# Bee_Hive_Scale_Board.net
KiCad netlist of a schematic drawn in Altium Designer
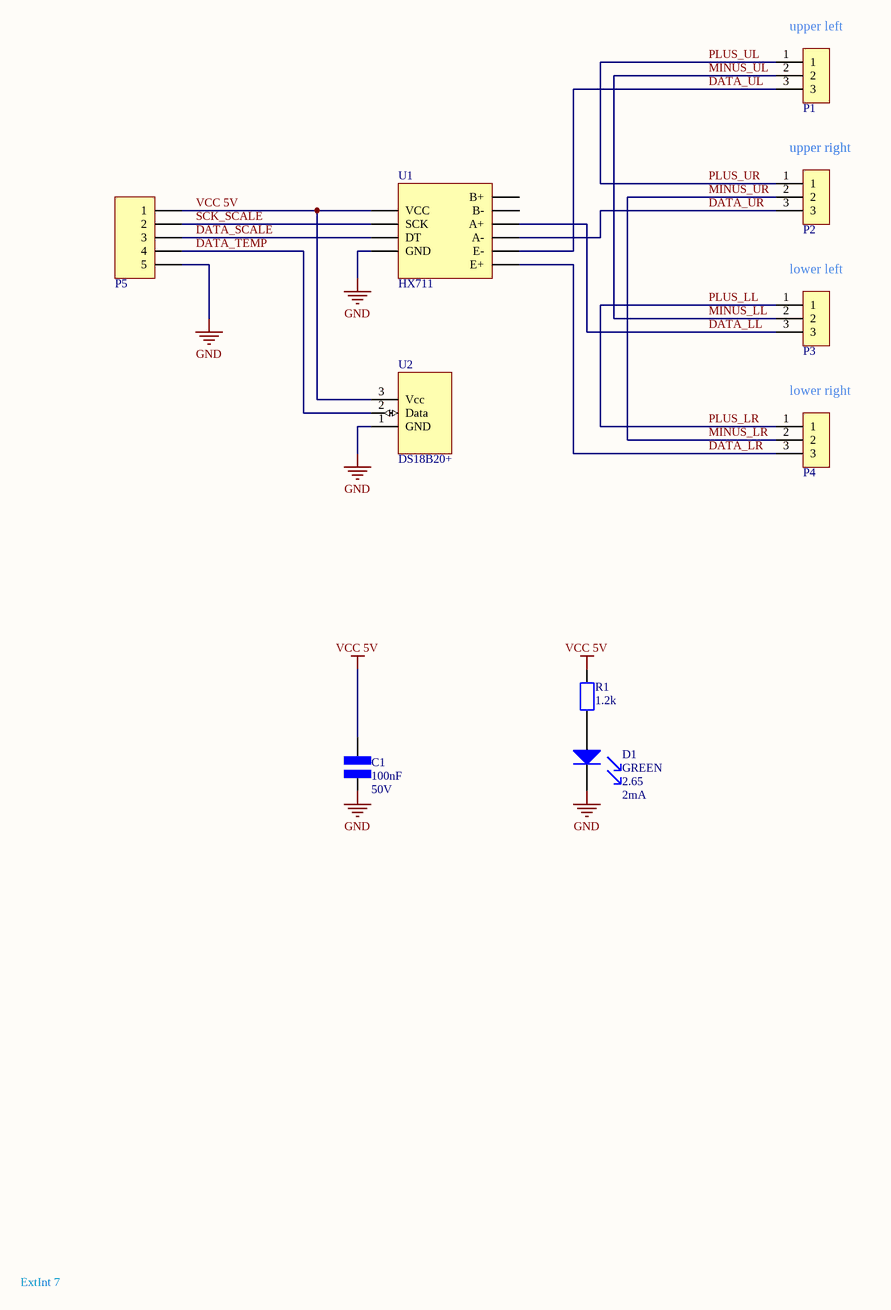
[diagram p0: Bee Hive Scale Board.SchDoc]

(export (version "E")
  (design (tool "Eeschema 10.0.6"))
  (components
    (comp (ref "C1")
      (value "100nF")
      (footprint "CAP 0603")
      (description "C CERAMIC SMD")
      (fields (field (name "UMAX") "50V") (field (name "Comment") "100nF 0603_1"))
      (libsource (lib "Library CAP") (part "100nF 0603_1"))
    )
    (comp (ref "D1")
      (value "LED Diode SMD LOW CURRENT")
      (footprint "LED SMD 0603 FOOTPRINT")
      (description "APT1608LZGCK")
      (fields
        (field (name "COLOR") "GREEN")
        (field (name "FORWARD VOLTAGE") "2.65")
        (field (name "IF") "2mA")
      )
      (libsource (lib "Library DIODE") (part "LED Diode SMD - GREEN - 0603 - 2mA_1"))
    )
    (comp (ref "P1")
      (value "3-Pin Right Angle Housing")
      (footprint "3PIN - Connector right angle")
      (description "3-Pin")
      (libsource (lib "Library Scematic") (part "3-Pin Right Angle"))
    )
    (comp (ref "P2")
      (value "3-Pin Right Angle Housing")
      (footprint "3PIN - Connector right angle")
      (description "3-Pin")
      (libsource (lib "Library Scematic") (part "3-Pin Right Angle"))
    )
    (comp (ref "P3")
      (value "3-Pin Right Angle Housing")
      (footprint "3PIN - Connector right angle")
      (description "3-Pin")
      (libsource (lib "Library Scematic") (part "3-Pin Right Angle"))
    )
    (comp (ref "P4")
      (value "3-Pin Right Angle Housing")
      (footprint "3PIN - Connector right angle")
      (description "3-Pin")
      (libsource (lib "Library Scematic") (part "3-Pin Right Angle"))
    )
    (comp (ref "P5")
      (value "comment")
      (footprint "5PIN")
      (description "5-Pin")
      (libsource (lib "Library Scematic") (part "5-Pin"))
    )
    (comp (ref "R1")
      (value "1.2k")
      (footprint "RES 0603 FOOTPRINT")
      (description "R SMD")
      (fields (field (name "Comment") "1.2k Ohm 0603"))
      (libsource (lib "Library RES") (part "1.2k Ohm 0603"))
    )
    (comp (ref "U1")
      (value "HX711")
      (footprint "HX711 SCALE")
      (description "HX711 XFW Alibaba Board")
      (libsource (lib "Library Scematic") (part "HX711 XFW Alibaba Board"))
    )
    (comp (ref "U2")
      (value "DS18B20+")
      (footprint "DS1820 Footprint")
      (description "Temperature Sensor, 12 Bit, OneWire, 3-pin TO-92")
      (libsource (lib "Library Scematic") (part "DS18B20"))
    )
  )
  (nets
    (net (code "1") (name "/DATA_LL") (class "Default")
      (node (ref "P3") (pin "3") (pinfunction "3_3") (pintype "passive"))
      (node (ref "U1") (pin "4") (pinfunction "A+_4") (pintype "passive"))
    )
    (net (code "2") (name "/DATA_LR") (class "Default")
      (node (ref "P4") (pin "3") (pinfunction "3_3") (pintype "passive"))
      (node (ref "U1") (pin "1") (pinfunction "E+_1") (pintype "passive"))
    )
    (net (code "3") (name "/DATA_SCALE") (class "Default")
      (node (ref "P5") (pin "3") (pinfunction "3_3") (pintype "passive"))
      (node (ref "U1") (pin "8") (pinfunction "DT_8") (pintype "passive"))
    )
    (net (code "4") (name "/DATA_TEMP") (class "Default")
      (node (ref "P5") (pin "4") (pinfunction "4_4") (pintype "passive"))
      (node (ref "U2") (pin "2") (pinfunction "Data_2") (pintype "bidirectional"))
    )
    (net (code "5") (name "/DATA_UL") (class "Default")
      (node (ref "P1") (pin "3") (pinfunction "3_3") (pintype "passive"))
      (node (ref "U1") (pin "2") (pinfunction "E-_2") (pintype "passive"))
    )
    (net (code "6") (name "/DATA_UR") (class "Default")
      (node (ref "P2") (pin "3") (pinfunction "3_3") (pintype "passive"))
      (node (ref "U1") (pin "3") (pinfunction "A-_3") (pintype "passive"))
    )
    (net (code "7") (name "/MINUS_LL") (class "Default")
      (node (ref "P1") (pin "2") (pinfunction "2_2") (pintype "passive"))
      (node (ref "P3") (pin "2") (pinfunction "2_2") (pintype "passive"))
    )
    (net (code "8") (name "/MINUS_LR") (class "Default")
      (node (ref "P2") (pin "2") (pinfunction "2_2") (pintype "passive"))
      (node (ref "P4") (pin "2") (pinfunction "2_2") (pintype "passive"))
    )
    (net (code "9") (name "/PLUS_LL") (class "Default")
      (node (ref "P3") (pin "1") (pinfunction "1_1") (pintype "passive"))
      (node (ref "P4") (pin "1") (pinfunction "1_1") (pintype "passive"))
    )
    (net (code "10") (name "/PLUS_UL") (class "Default")
      (node (ref "P1") (pin "1") (pinfunction "1_1") (pintype "passive"))
      (node (ref "P2") (pin "1") (pinfunction "1_1") (pintype "passive"))
    )
    (net (code "11") (name "/SCK_SCALE") (class "Default")
      (node (ref "P5") (pin "2") (pinfunction "2_2") (pintype "passive"))
      (node (ref "U1") (pin "9") (pinfunction "SCK_9") (pintype "passive"))
    )
    (net (code "12") (name "GND") (class "Default")
      (node (ref "C1") (pin "1") (pinfunction "1_1") (pintype "passive"))
      (node (ref "D1") (pin "2") (pinfunction "K_2") (pintype "passive"))
      (node (ref "P5") (pin "5") (pinfunction "5_5") (pintype "passive"))
      (node (ref "U1") (pin "7") (pinfunction "GND_7") (pintype "passive"))
      (node (ref "U2") (pin "1") (pinfunction "GND_1") (pintype "power_in"))
    )
    (net (code "13") (name "Net-(D1-A)") (class "Default")
      (node (ref "D1") (pin "1") (pinfunction "A_1") (pintype "passive"))
      (node (ref "R1") (pin "1") (pinfunction "1_1") (pintype "passive"))
    )
    (net (code "14") (name "VCC 5V") (class "Default")
      (node (ref "C1") (pin "2") (pinfunction "2_2") (pintype "passive"))
      (node (ref "P5") (pin "1") (pinfunction "1_1") (pintype "passive"))
      (node (ref "R1") (pin "2") (pinfunction "2_2") (pintype "passive"))
      (node (ref "U1") (pin "10") (pinfunction "VCC_10") (pintype "passive"))
      (node (ref "U2") (pin "3") (pinfunction "Vcc_3") (pintype "power_in"))
    )
    (net (code "15") (name "unconnected-(U1-B+-Pad6)") (class "Default")
      (node (ref "U1") (pin "6") (pinfunction "B+_6") (pintype "passive"))
    )
    (net (code "16") (name "unconnected-(U1-B--Pad5)") (class "Default")
      (node (ref "U1") (pin "5") (pinfunction "B-_5") (pintype "passive"))
    )
  )
)
